# IGauge_V_2_1.net
KiCad netlist of a schematic drawn in EAGLE
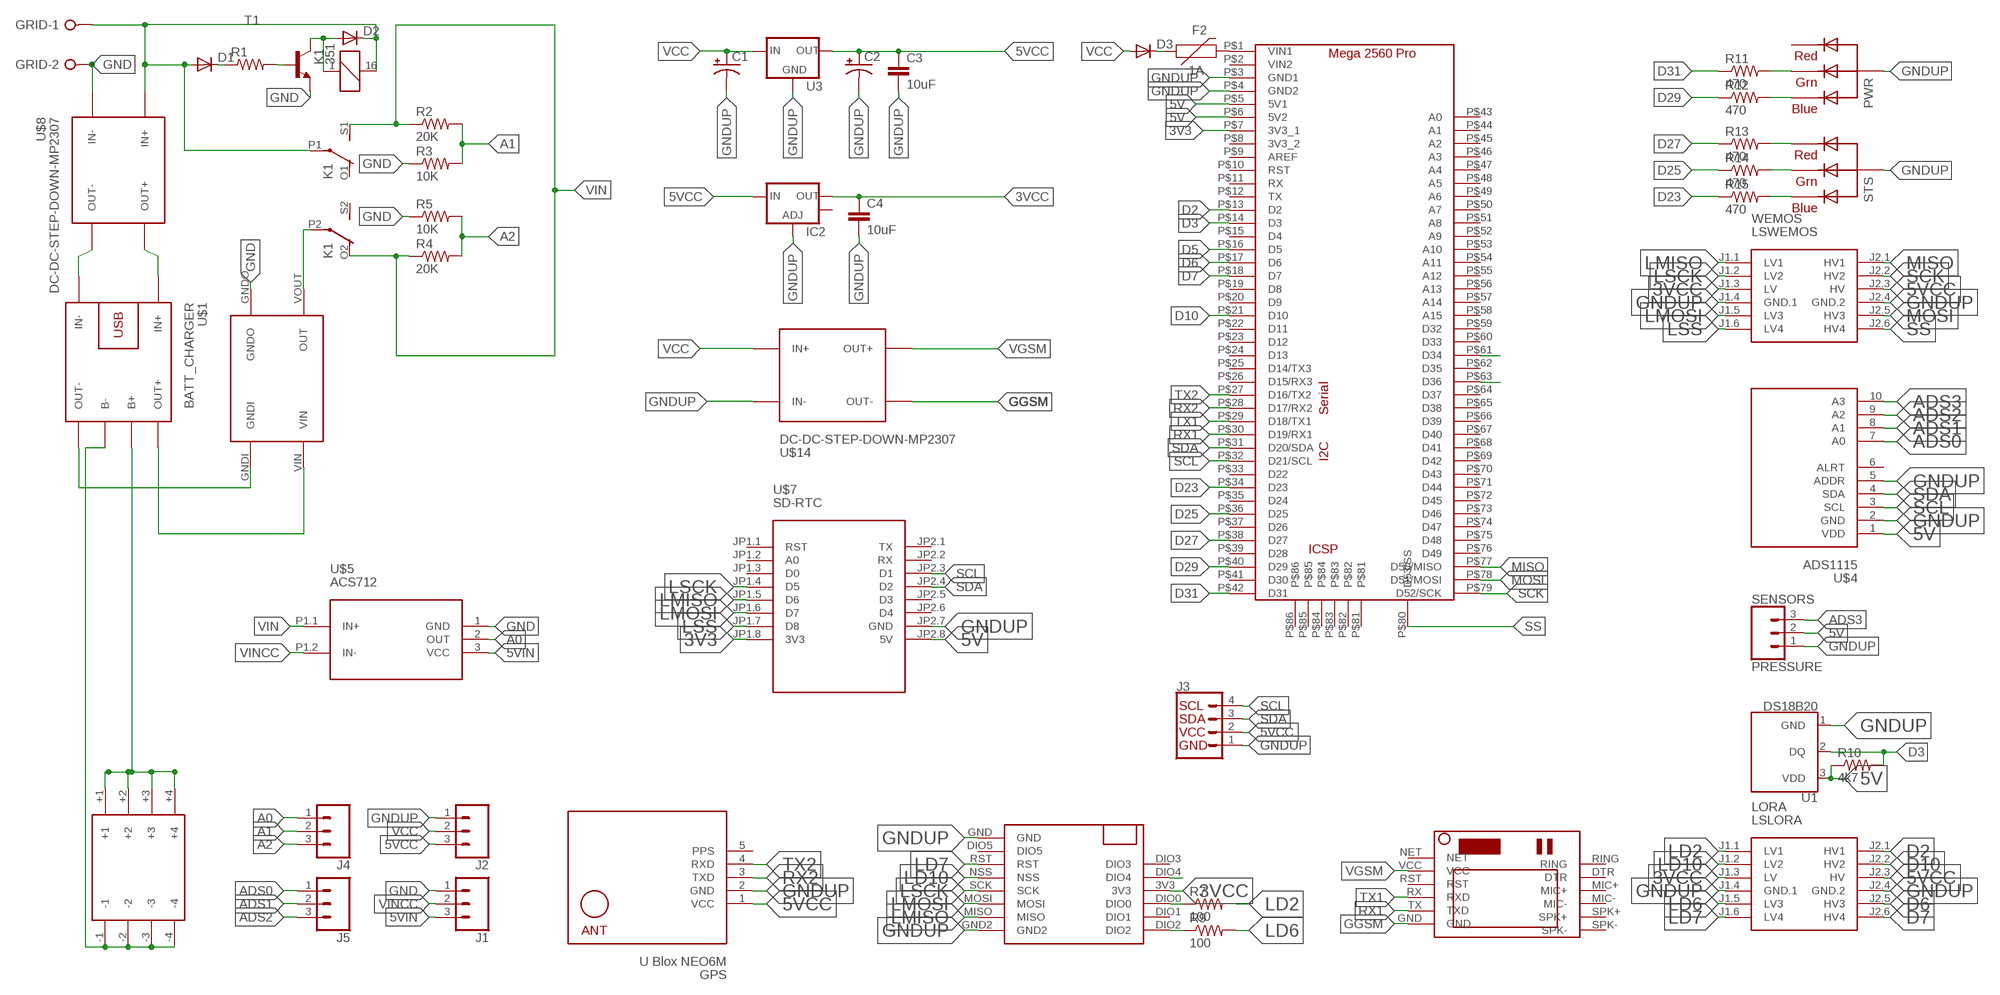
[diagram p0: schematic, sheet 1]

(export (version "E")
  (design (tool "Eeschema 10.0.6"))
  (components
    (comp (ref "C1")
      (value "CPOL-USD")
      (footprint "eagle-import:PANASONIC_D")
      (libsource (lib "eagle-import") (part "CPOL-USD"))
    )
    (comp (ref "C2")
      (value "CPOL-USD")
      (footprint "eagle-import:PANASONIC_D")
      (libsource (lib "eagle-import") (part "CPOL-USD"))
    )
    (comp (ref "C3")
      (value "10uF")
      (footprint "eagle-import:1206")
      (libsource (lib "eagle-import") (part "10UF-1206-6.3V-20%"))
    )
    (comp (ref "C4")
      (value "10uF")
      (footprint "eagle-import:1206")
      (libsource (lib "eagle-import") (part "10UF-1206-6.3V-20%"))
    )
    (comp (ref "D1")
      (value "DIODE-SOD106A-R")
      (footprint "eagle-import:SOD106A-R")
      (libsource (lib "eagle-import") (part "DIODE-SOD106A-R"))
    )
    (comp (ref "D2")
      (value "DIODE-SOD106A-R")
      (footprint "eagle-import:SOD106A-R")
      (libsource (lib "eagle-import") (part "DIODE-SOD106A-R"))
    )
    (comp (ref "D3")
      (value "DIODE-SOD106A-R")
      (footprint "eagle-import:SOD106A-R")
      (libsource (lib "eagle-import") (part "DIODE-SOD106A-R"))
    )
    (comp (ref "F2")
      (value "1A")
      (footprint "eagle-import:1206")
      (libsource (lib "eagle-import") (part "PPTC_HALF-AMP"))
    )
    (comp (ref "GPS")
      (value "U Blox NEO6M")
      (footprint "eagle-import:GPS-RECEIVER-NEO6M")
      (libsource (lib "eagle-import") (part "GPS-RECEIVER-NEO6M"))
    )
    (comp (ref "GRID")
      (value "W237-02P")
      (footprint "eagle-import:W237-132")
      (libsource (lib "eagle-import") (part "W237-02P"))
    )
    (comp (ref "IC2")
      (value "V_REG_LM1117SOT223")
      (footprint "eagle-import:SOT223")
      (libsource (lib "eagle-import") (part "V_REG_LM1117SOT223"))
    )
    (comp (ref "J1")
      (value "CONN_03")
      (footprint "eagle-import:1X03")
      (libsource (lib "eagle-import") (part "CONN_03"))
    )
    (comp (ref "J2")
      (value "CONN_03")
      (footprint "eagle-import:1X03")
      (libsource (lib "eagle-import") (part "CONN_03"))
    )
    (comp (ref "J3")
      (value "I2C_STANDARD")
      (footprint "eagle-import:1X04")
      (libsource (lib "eagle-import") (part "I2C_STANDARD"))
    )
    (comp (ref "J4")
      (value "CONN_03")
      (footprint "eagle-import:1X03")
      (libsource (lib "eagle-import") (part "CONN_03"))
    )
    (comp (ref "J5")
      (value "CONN_03")
      (footprint "eagle-import:1X03")
      (libsource (lib "eagle-import") (part "CONN_03"))
    )
    (comp (ref "K1")
      (value "351")
      (footprint "eagle-import:351")
      (libsource (lib "eagle-import") (part "351"))
    )
    (comp (ref "LORA")
      (value "LSLORA")
      (footprint "eagle-import:LEVEL-SHIFTER-4CH")
      (libsource (lib "eagle-import") (part "LEVEL-SHIFTER-4CH"))
    )
    (comp (ref "PWR")
      (value "RGBLED_CA-5MM")
      (footprint "eagle-import:LED5MMRGB")
      (libsource (lib "eagle-import") (part "RGBLED_CA-5MM"))
    )
    (comp (ref "R1")
      (value "R-US_R1206")
      (footprint "eagle-import:R1206")
      (libsource (lib "eagle-import") (part "resistor_R-US_R1206"))
    )
    (comp (ref "R2")
      (value "20K")
      (footprint "eagle-import:R1206")
      (libsource (lib "eagle-import") (part "resistor_R-US_R1206"))
    )
    (comp (ref "R3")
      (value "10K")
      (footprint "eagle-import:R1206")
      (libsource (lib "eagle-import") (part "resistor_R-US_R1206"))
    )
    (comp (ref "R4")
      (value "20K")
      (footprint "eagle-import:R1206")
      (libsource (lib "eagle-import") (part "resistor_R-US_R1206"))
    )
    (comp (ref "R5")
      (value "10K")
      (footprint "eagle-import:R1206")
      (libsource (lib "eagle-import") (part "resistor_R-US_R1206"))
    )
    (comp (ref "R7")
      (value "100")
      (footprint "eagle-import:M1406")
      (libsource (lib "eagle-import") (part "R-US_M1406"))
    )
    (comp (ref "R9")
      (value "100")
      (footprint "eagle-import:M1406")
      (libsource (lib "eagle-import") (part "R-US_M1406"))
    )
    (comp (ref "R10")
      (value "4k7")
      (footprint "eagle-import:M1406")
      (libsource (lib "eagle-import") (part "R-US_M1406"))
    )
    (comp (ref "R11")
      (value "470")
      (footprint "eagle-import:R1206")
      (libsource (lib "eagle-import") (part "resistor_R-US_R1206"))
    )
    (comp (ref "R12")
      (value "470")
      (footprint "eagle-import:R1206")
      (libsource (lib "eagle-import") (part "resistor_R-US_R1206"))
    )
    (comp (ref "R13")
      (value "470")
      (footprint "eagle-import:R1206")
      (libsource (lib "eagle-import") (part "resistor_R-US_R1206"))
    )
    (comp (ref "R14")
      (value "470")
      (footprint "eagle-import:R1206")
      (libsource (lib "eagle-import") (part "resistor_R-US_R1206"))
    )
    (comp (ref "R15")
      (value "470")
      (footprint "eagle-import:R1206")
      (libsource (lib "eagle-import") (part "resistor_R-US_R1206"))
    )
    (comp (ref "SENSORS")
      (value "PRESSURE")
      (footprint "eagle-import:MOLEX-1X3")
      (libsource (lib "eagle-import") (part "CONN_03POLAR"))
    )
    (comp (ref "STS")
      (value "RGBLED_CA-5MM")
      (footprint "eagle-import:LED5MMRGB")
      (libsource (lib "eagle-import") (part "RGBLED_CA-5MM"))
    )
    (comp (ref "T1")
      (value "-NPN-SOT23-EBC")
      (footprint "eagle-import:SOT23-EBC")
      (libsource (lib "eagle-import") (part "-NPN-SOT23-EBC"))
    )
    (comp (ref "U$1")
      (value "BATT_CHARGER")
      (footprint "eagle-import:BATTERY-CHARGER-LI-PROT")
      (libsource (lib "eagle-import") (part "BATTERY-CHARGER-LI-PROT"))
    )
    (comp (ref "U$2")
      (value "MT360_STEPUP")
      (footprint "eagle-import:MT360_STEPUP")
      (libsource (lib "eagle-import") (part "MT360_STEPUP"))
    )
    (comp (ref "U$3")
      (value "MEGAPROMINI")
      (footprint "eagle-import:MEGAPROMINI")
      (libsource (lib "eagle-import") (part "MEGAPROMINI"))
    )
    (comp (ref "U$4")
      (value "ADS1115")
      (footprint "eagle-import:ADC-4CH-ADS1115")
      (libsource (lib "eagle-import") (part "ADC-4CH-ADS1115"))
    )
    (comp (ref "U$5")
      (value "ACS712")
      (footprint "eagle-import:CURRENT-SENSOR-ACS712#IC")
      (libsource (lib "eagle-import") (part "CURRENT-SENSOR-ACS712#IC"))
    )
    (comp (ref "U$6")
      (value "LORA915MHZ")
      (footprint "eagle-import:LORA915MHZ")
      (libsource (lib "eagle-import") (part "LORA915MHZ"))
    )
    (comp (ref "U$7")
      (value "SD-RTC")
      (footprint "eagle-import:WEMOS-D1-MINI-SHIELD")
      (libsource (lib "eagle-import") (part "WEMOS-D1-MINI-SHIELD"))
    )
    (comp (ref "U$8")
      (value "DC-DC-STEP-DOWN-MP2307")
      (footprint "eagle-import:DC-DC-STEP-DOWN-MP2307")
      (libsource (lib "eagle-import") (part "DC-DC-STEP-DOWN-MP2307"))
    )
    (comp (ref "U$9")
      (value "18650_4PCS_BATTERY_HOLDER")
      (footprint "eagle-import:18650_4PCS_BATTERY_HOLDER")
      (libsource (lib "eagle-import") (part "18650_4PCS_BATTERY_HOLDER"))
    )
    (comp (ref "U$10")
      (value "SIM800LMODULE")
      (footprint "eagle-import:SIM800LMODULE")
      (libsource (lib "eagle-import") (part "SIM800LMODULE"))
    )
    (comp (ref "U$14")
      (value "DC-DC-STEP-DOWN-MP2307")
      (footprint "eagle-import:DC-DC-STEP-DOWN-MP2307")
      (libsource (lib "eagle-import") (part "DC-DC-STEP-DOWN-MP2307"))
    )
    (comp (ref "U1")
      (value "DS18B20")
      (footprint "eagle-import:TO-92-AMMO")
      (libsource (lib "eagle-import") (part "DS18B20"))
    )
    (comp (ref "U3")
      (value "V_REG_78XX-TO-220")
      (footprint "eagle-import:TO-220-ALT")
      (libsource (lib "eagle-import") (part "V_REG_78XX-TO-220"))
    )
    (comp (ref "WEMOS")
      (value "LSWEMOS")
      (footprint "eagle-import:LEVEL-SHIFTER-4CH")
      (libsource (lib "eagle-import") (part "LEVEL-SHIFTER-4CH"))
    )
  )
  (nets
    (net (code "1") (name "/PPS") (class "Default")
      (node (ref "GPS") (pin "5") (pinfunction "PPS_5") (pintype "power_in"))
    )
    (net (code "2") (name "3V3") (class "Default")
      (node (ref "U$3") (pin "P$7") (pinfunction "3V3_1_P$7") (pintype "bidirectional"))
      (node (ref "U$7") (pin "JP1.8") (pinfunction "3V3_JP1.8") (pintype "power_in"))
    )
    (net (code "3") (name "3VCC") (class "Default")
      (node (ref "C4") (pin "1") (pinfunction "1_1") (pintype "passive"))
      (node (ref "IC2") (pin "2") (pinfunction "OUT_2") (pintype "output"))
      (node (ref "LORA") (pin "J1.3") (pinfunction "LV_J1.3") (pintype "power_in"))
      (node (ref "U$6") (pin "3V3") (pinfunction "3V3_3V3") (pintype "bidirectional"))
      (node (ref "WEMOS") (pin "J1.3") (pinfunction "LV_J1.3") (pintype "power_in"))
    )
    (net (code "4") (name "5V") (class "Default")
      (node (ref "R10") (pin "1") (pinfunction "1_1") (pintype "passive"))
      (node (ref "SENSORS") (pin "2") (pinfunction "2_2") (pintype "passive"))
      (node (ref "U$3") (pin "P$5") (pinfunction "5V1_P$5") (pintype "bidirectional"))
      (node (ref "U$3") (pin "P$6") (pinfunction "5V2_P$6") (pintype "bidirectional"))
      (node (ref "U$4") (pin "1") (pinfunction "VDD_1") (pintype "power_in"))
      (node (ref "U$7") (pin "JP2.8") (pinfunction "5V_JP2.8") (pintype "power_in"))
      (node (ref "U1") (pin "3") (pinfunction "VDD_3") (pintype "power_in"))
    )
    (net (code "5") (name "5VCC") (class "Default")
      (node (ref "C2") (pin "+") (pinfunction "+_+") (pintype "passive"))
      (node (ref "C3") (pin "1") (pinfunction "1_1") (pintype "passive"))
      (node (ref "GPS") (pin "1") (pinfunction "VCC_1") (pintype "bidirectional"))
      (node (ref "IC2") (pin "3") (pinfunction "IN_3") (pintype "input"))
      (node (ref "J2") (pin "3") (pinfunction "3_3") (pintype "passive"))
      (node (ref "J3") (pin "2") (pinfunction "2_2") (pintype "power_in"))
      (node (ref "LORA") (pin "J2.3") (pinfunction "HV_J2.3") (pintype "power_in"))
      (node (ref "U3") (pin "OUT") (pinfunction "OUT_OUT") (pintype "passive"))
      (node (ref "WEMOS") (pin "J2.3") (pinfunction "HV_J2.3") (pintype "power_in"))
    )
    (net (code "6") (name "5VIN") (class "Default")
      (node (ref "J1") (pin "3") (pinfunction "3_3") (pintype "passive"))
      (node (ref "U$5") (pin "3") (pinfunction "VCC_3") (pintype "power_in"))
    )
    (net (code "7") (name "A0") (class "Default")
      (node (ref "J4") (pin "1") (pinfunction "1_1") (pintype "passive"))
      (node (ref "U$5") (pin "2") (pinfunction "OUT_2") (pintype "output"))
    )
    (net (code "8") (name "A1") (class "Default")
      (node (ref "J4") (pin "2") (pinfunction "2_2") (pintype "passive"))
      (node (ref "R2") (pin "2") (pinfunction "2_2") (pintype "passive"))
      (node (ref "R3") (pin "2") (pinfunction "2_2") (pintype "passive"))
    )
    (net (code "9") (name "A2") (class "Default")
      (node (ref "J4") (pin "3") (pinfunction "3_3") (pintype "passive"))
      (node (ref "R4") (pin "2") (pinfunction "2_2") (pintype "passive"))
      (node (ref "R5") (pin "2") (pinfunction "2_2") (pintype "passive"))
    )
    (net (code "10") (name "ADS0") (class "Default")
      (node (ref "J5") (pin "1") (pinfunction "1_1") (pintype "passive"))
      (node (ref "U$4") (pin "7") (pinfunction "A0_7") (pintype "input"))
    )
    (net (code "11") (name "ADS1") (class "Default")
      (node (ref "J5") (pin "2") (pinfunction "2_2") (pintype "passive"))
      (node (ref "U$4") (pin "8") (pinfunction "A1_8") (pintype "input"))
    )
    (net (code "12") (name "ADS2") (class "Default")
      (node (ref "J5") (pin "3") (pinfunction "3_3") (pintype "passive"))
      (node (ref "U$4") (pin "9") (pinfunction "A2_9") (pintype "input"))
    )
    (net (code "13") (name "ADS3") (class "Default")
      (node (ref "SENSORS") (pin "3") (pinfunction "3_3") (pintype "passive"))
      (node (ref "U$4") (pin "10") (pinfunction "A3_10") (pintype "input"))
    )
    (net (code "14") (name "D2") (class "Default")
      (node (ref "LORA") (pin "J2.1") (pinfunction "HV1_J2.1") (pintype "bidirectional"))
      (node (ref "U$3") (pin "P$13") (pinfunction "D2_P$13") (pintype "bidirectional"))
    )
    (net (code "15") (name "D3") (class "Default")
      (node (ref "R10") (pin "2") (pinfunction "2_2") (pintype "passive"))
      (node (ref "U$3") (pin "P$14") (pinfunction "D3_P$14") (pintype "bidirectional"))
      (node (ref "U1") (pin "2") (pinfunction "DQ_2") (pintype "bidirectional"))
    )
    (net (code "16") (name "D5") (class "Default")
      (node (ref "U$3") (pin "P$16") (pinfunction "D5_P$16") (pintype "bidirectional"))
    )
    (net (code "17") (name "D6") (class "Default")
      (node (ref "LORA") (pin "J2.5") (pinfunction "HV3_J2.5") (pintype "bidirectional"))
      (node (ref "U$3") (pin "P$17") (pinfunction "D6_P$17") (pintype "bidirectional"))
    )
    (net (code "18") (name "D7") (class "Default")
      (node (ref "LORA") (pin "J2.6") (pinfunction "HV4_J2.6") (pintype "bidirectional"))
      (node (ref "U$3") (pin "P$18") (pinfunction "D7_P$18") (pintype "bidirectional"))
    )
    (net (code "19") (name "D10") (class "Default")
      (node (ref "LORA") (pin "J2.2") (pinfunction "HV2_J2.2") (pintype "bidirectional"))
      (node (ref "U$3") (pin "P$21") (pinfunction "D10_P$21") (pintype "bidirectional"))
    )
    (net (code "20") (name "D23") (class "Default")
      (node (ref "R15") (pin "1") (pinfunction "1_1") (pintype "passive"))
      (node (ref "U$3") (pin "P$34") (pinfunction "D23_P$34") (pintype "bidirectional"))
    )
    (net (code "21") (name "D25") (class "Default")
      (node (ref "R14") (pin "1") (pinfunction "1_1") (pintype "passive"))
      (node (ref "U$3") (pin "P$36") (pinfunction "D25_P$36") (pintype "bidirectional"))
    )
    (net (code "22") (name "D27") (class "Default")
      (node (ref "R13") (pin "1") (pinfunction "1_1") (pintype "passive"))
      (node (ref "U$3") (pin "P$38") (pinfunction "D27_P$38") (pintype "bidirectional"))
    )
    (net (code "23") (name "D29") (class "Default")
      (node (ref "R12") (pin "1") (pinfunction "1_1") (pintype "passive"))
      (node (ref "U$3") (pin "P$40") (pinfunction "D29_P$40") (pintype "bidirectional"))
    )
    (net (code "24") (name "D31") (class "Default")
      (node (ref "R11") (pin "1") (pinfunction "1_1") (pintype "passive"))
      (node (ref "U$3") (pin "P$42") (pinfunction "D31_P$42") (pintype "bidirectional"))
    )
    (net (code "25") (name "GGSM") (class "Default")
      (node (ref "U$10") (pin "GND") (pinfunction "GND_GND") (pintype "bidirectional"))
      (node (ref "U$14") (pin "OUT-") (pinfunction "OUT-_OUT-") (pintype "bidirectional"))
    )
    (net (code "26") (name "GND") (class "Default")
      (node (ref "D1") (pin "A") (pinfunction "A_A") (pintype "passive"))
      (node (ref "D2") (pin "C") (pinfunction "C_C") (pintype "passive"))
      (node (ref "GRID") (pin "1") (pinfunction "KL_1") (pintype "passive"))
      (node (ref "GRID") (pin "2") (pinfunction "KL_2") (pintype "passive"))
      (node (ref "J1") (pin "1") (pinfunction "1_1") (pintype "passive"))
      (node (ref "K1") (pin "16") (pinfunction "2_16") (pintype "passive"))
      (node (ref "K1") (pin "P1") (pinfunction "P_P1") (pintype "passive"))
      (node (ref "R3") (pin "1") (pinfunction "1_1") (pintype "passive"))
      (node (ref "R5") (pin "1") (pinfunction "1_1") (pintype "passive"))
      (node (ref "T1") (pin "E") (pinfunction "E_E") (pintype "passive"))
      (node (ref "U$2") (pin "GNDO") (pinfunction "GNDO_GNDO") (pintype "bidirectional"))
      (node (ref "U$5") (pin "1") (pinfunction "GND_1") (pintype "power_in"))
      (node (ref "U$8") (pin "IN+") (pinfunction "IN+_IN+") (pintype "bidirectional"))
      (node (ref "U$8") (pin "IN-") (pinfunction "IN-_IN-") (pintype "bidirectional"))
    )
    (net (code "27") (name "GNDUP") (class "Default")
      (node (ref "C1") (pin "-") (pinfunction "-_-") (pintype "passive"))
      (node (ref "C2") (pin "-") (pinfunction "-_-") (pintype "passive"))
      (node (ref "C3") (pin "2") (pinfunction "2_2") (pintype "passive"))
      (node (ref "C4") (pin "2") (pinfunction "2_2") (pintype "passive"))
      (node (ref "GPS") (pin "2") (pinfunction "GND_2") (pintype "bidirectional"))
      (node (ref "IC2") (pin "1") (pinfunction "ADJ_1") (pintype "input"))
      (node (ref "J2") (pin "1") (pinfunction "1_1") (pintype "passive"))
      (node (ref "J3") (pin "1") (pinfunction "1_1") (pintype "power_in"))
      (node (ref "LORA") (pin "J1.4") (pinfunction "GND.1_J1.4") (pintype "power_in"))
      (node (ref "LORA") (pin "J2.4") (pinfunction "GND.2_J2.4") (pintype "power_in"))
      (node (ref "PWR") (pin "2") (pinfunction "VCC_2") (pintype "bidirectional"))
      (node (ref "SENSORS") (pin "1") (pinfunction "1_1") (pintype "passive"))
      (node (ref "STS") (pin "2") (pinfunction "VCC_2") (pintype "bidirectional"))
      (node (ref "U$1") (pin "IN-") (pinfunction "IN-_IN-") (pintype "bidirectional"))
      (node (ref "U$14") (pin "IN-") (pinfunction "IN-_IN-") (pintype "bidirectional"))
      (node (ref "U$3") (pin "P$3") (pinfunction "GND1_P$3") (pintype "bidirectional"))
      (node (ref "U$3") (pin "P$4") (pinfunction "GND2_P$4") (pintype "bidirectional"))
      (node (ref "U$4") (pin "2") (pinfunction "GND_2") (pintype "power_in"))
      (node (ref "U$4") (pin "5") (pinfunction "ADDR_5") (pintype "bidirectional"))
      (node (ref "U$6") (pin "GND") (pinfunction "GND_GND") (pintype "bidirectional"))
      (node (ref "U$6") (pin "GND2") (pinfunction "GND2_GND2") (pintype "bidirectional"))
      (node (ref "U$7") (pin "JP2.7") (pinfunction "GND_JP2.7") (pintype "power_in"))
      (node (ref "U$8") (pin "OUT-") (pinfunction "OUT-_OUT-") (pintype "bidirectional"))
      (node (ref "U1") (pin "1") (pinfunction "GND_1") (pintype "power_in"))
      (node (ref "U3") (pin "GND") (pinfunction "GND_GND") (pintype "input"))
      (node (ref "WEMOS") (pin "J1.4") (pinfunction "GND.1_J1.4") (pintype "power_in"))
      (node (ref "WEMOS") (pin "J2.4") (pinfunction "GND.2_J2.4") (pintype "power_in"))
    )
    (net (code "28") (name "LD2") (class "Default")
      (node (ref "LORA") (pin "J1.1") (pinfunction "LV1_J1.1") (pintype "bidirectional"))
      (node (ref "R7") (pin "2") (pinfunction "2_2") (pintype "passive"))
    )
    (net (code "29") (name "LD6") (class "Default")
      (node (ref "LORA") (pin "J1.5") (pinfunction "LV3_J1.5") (pintype "bidirectional"))
      (node (ref "R9") (pin "2") (pinfunction "2_2") (pintype "passive"))
    )
    (net (code "30") (name "LD7") (class "Default")
      (node (ref "LORA") (pin "J1.6") (pinfunction "LV4_J1.6") (pintype "bidirectional"))
      (node (ref "U$6") (pin "RST") (pinfunction "RST_RST") (pintype "bidirectional"))
    )
    (net (code "31") (name "LD10") (class "Default")
      (node (ref "LORA") (pin "J1.2") (pinfunction "LV2_J1.2") (pintype "bidirectional"))
      (node (ref "U$6") (pin "NSS") (pinfunction "NSS_NSS") (pintype "bidirectional"))
    )
    (net (code "32") (name "LMISO") (class "Default")
      (node (ref "U$6") (pin "MISO") (pinfunction "MISO_MISO") (pintype "bidirectional"))
      (node (ref "U$7") (pin "JP1.5") (pinfunction "D6_JP1.5") (pintype "bidirectional"))
      (node (ref "WEMOS") (pin "J1.1") (pinfunction "LV1_J1.1") (pintype "bidirectional"))
    )
    (net (code "33") (name "LMOSI") (class "Default")
      (node (ref "U$6") (pin "MOSI") (pinfunction "MOSI_MOSI") (pintype "bidirectional"))
      (node (ref "U$7") (pin "JP1.6") (pinfunction "D7_JP1.6") (pintype "bidirectional"))
      (node (ref "WEMOS") (pin "J1.5") (pinfunction "LV3_J1.5") (pintype "bidirectional"))
    )
    (net (code "34") (name "LSCK") (class "Default")
      (node (ref "U$6") (pin "SCK") (pinfunction "SCK_SCK") (pintype "bidirectional"))
      (node (ref "U$7") (pin "JP1.4") (pinfunction "D5_JP1.4") (pintype "bidirectional"))
      (node (ref "WEMOS") (pin "J1.2") (pinfunction "LV2_J1.2") (pintype "bidirectional"))
    )
    (net (code "35") (name "LSS") (class "Default")
      (node (ref "U$7") (pin "JP1.7") (pinfunction "D8_JP1.7") (pintype "bidirectional"))
      (node (ref "WEMOS") (pin "J1.6") (pinfunction "LV4_J1.6") (pintype "bidirectional"))
    )
    (net (code "36") (name "MISO") (class "Default")
      (node (ref "U$3") (pin "P$77") (pinfunction "D50/MISO_P$77") (pintype "bidirectional"))
      (node (ref "WEMOS") (pin "J2.1") (pinfunction "HV1_J2.1") (pintype "bidirectional"))
    )
    (net (code "37") (name "MOSI") (class "Default")
      (node (ref "U$3") (pin "P$78") (pinfunction "D51/MOSI_P$78") (pintype "bidirectional"))
      (node (ref "WEMOS") (pin "J2.5") (pinfunction "HV3_J2.5") (pintype "bidirectional"))
    )
    (net (code "38") (name "Net-(D1-PadC)") (class "Default")
      (node (ref "D1") (pin "C") (pinfunction "C_C") (pintype "passive"))
      (node (ref "R1") (pin "1") (pinfunction "1_1") (pintype "passive"))
    )
    (net (code "39") (name "Net-(D2-PadA)") (class "Default")
      (node (ref "D2") (pin "A") (pinfunction "A_A") (pintype "passive"))
      (node (ref "K1") (pin "1") (pinfunction "1_1") (pintype "passive"))
      (node (ref "T1") (pin "C") (pinfunction "C_C") (pintype "passive"))
    )
    (net (code "40") (name "Net-(D3-PadC)") (class "Default")
      (node (ref "D3") (pin "C") (pinfunction "C_C") (pintype "passive"))
      (node (ref "F2") (pin "1") (pinfunction "1_1") (pintype "bidirectional"))
    )
    (net (code "41") (name "Net-(K1C-P)") (class "Default")
      (node (ref "K1") (pin "P2") (pinfunction "P_P2") (pintype "passive"))
      (node (ref "U$2") (pin "VOUT") (pinfunction "OUT_VOUT") (pintype "bidirectional"))
    )
    (net (code "42") (name "Net-(PWR-BLUE)") (class "Default")
      (node (ref "PWR") (pin "4") (pinfunction "BLUE_4") (pintype "bidirectional"))
      (node (ref "R12") (pin "2") (pinfunction "2_2") (pintype "passive"))
    )
    (net (code "43") (name "Net-(PWR-GREEN)") (class "Default")
      (node (ref "PWR") (pin "3") (pinfunction "GREEN_3") (pintype "bidirectional"))
      (node (ref "R11") (pin "2") (pinfunction "2_2") (pintype "passive"))
    )
    (net (code "44") (name "Net-(R1-Pad2)") (class "Default")
      (node (ref "R1") (pin "2") (pinfunction "2_2") (pintype "passive"))
      (node (ref "T1") (pin "B") (pinfunction "B_B") (pintype "passive"))
    )
    (net (code "45") (name "Net-(R7-Pad1)") (class "Default")
      (node (ref "R7") (pin "1") (pinfunction "1_1") (pintype "passive"))
      (node (ref "U$6") (pin "DIO0") (pinfunction "DIO0_DIO0") (pintype "bidirectional"))
    )
    (net (code "46") (name "Net-(R9-Pad1)") (class "Default")
      (node (ref "R9") (pin "1") (pinfunction "1_1") (pintype "passive"))
      (node (ref "U$6") (pin "DIO2") (pinfunction "DIO2_DIO2") (pintype "bidirectional"))
    )
    (net (code "47") (name "Net-(STS-BLUE)") (class "Default")
      (node (ref "R15") (pin "2") (pinfunction "2_2") (pintype "passive"))
      (node (ref "STS") (pin "4") (pinfunction "BLUE_4") (pintype "bidirectional"))
    )
    (net (code "48") (name "Net-(STS-GREEN)") (class "Default")
      (node (ref "R14") (pin "2") (pinfunction "2_2") (pintype "passive"))
      (node (ref "STS") (pin "3") (pinfunction "GREEN_3") (pintype "bidirectional"))
    )
    (net (code "49") (name "Net-(STS-RED)") (class "Default")
      (node (ref "R13") (pin "2") (pinfunction "2_2") (pintype "passive"))
      (node (ref "STS") (pin "1") (pinfunction "RED_1") (pintype "bidirectional"))
    )
    (net (code "50") (name "Net-(U$1-PadB+)") (class "Default")
      (node (ref "U$1") (pin "B+") (pinfunction "B+_B+") (pintype "bidirectional"))
      (node (ref "U$9") (pin "+1") (pinfunction "+1_+1") (pintype "bidirectional"))
      (node (ref "U$9") (pin "+2") (pinfunction "+2_+2") (pintype "bidirectional"))
      (node (ref "U$9") (pin "+3") (pinfunction "+3_+3") (pintype "bidirectional"))
      (node (ref "U$9") (pin "+4") (pinfunction "+4_+4") (pintype "bidirectional"))
    )
    (net (code "51") (name "Net-(U$1-PadB-)") (class "Default")
      (node (ref "U$1") (pin "B-") (pinfunction "B-_B-") (pintype "bidirectional"))
      (node (ref "U$9") (pin "-1") (pinfunction "-1_-1") (pintype "bidirectional"))
      (node (ref "U$9") (pin "-2") (pinfunction "-2_-2") (pintype "bidirectional"))
      (node (ref "U$9") (pin "-3") (pinfunction "-3_-3") (pintype "bidirectional"))
      (node (ref "U$9") (pin "-4") (pinfunction "-4_-4") (pintype "bidirectional"))
    )
    (net (code "52") (name "Net-(U$1-PadIN+)") (class "Default")
      (node (ref "U$1") (pin "IN+") (pinfunction "IN+_IN+") (pintype "bidirectional"))
      (node (ref "U$8") (pin "OUT+") (pinfunction "OUT+_OUT+") (pintype "bidirectional"))
    )
    (net (code "53") (name "Net-(U$1-PadOUT+)") (class "Default")
      (node (ref "U$1") (pin "OUT+") (pinfunction "OUT+_OUT+") (pintype "bidirectional"))
      (node (ref "U$2") (pin "VIN") (pinfunction "VIN_VIN") (pintype "bidirectional"))
    )
    (net (code "54") (name "Net-(U$1-PadOUT-)") (class "Default")
      (node (ref "U$1") (pin "OUT-") (pinfunction "OUT-_OUT-") (pintype "bidirectional"))
      (node (ref "U$2") (pin "GNDI") (pinfunction "GNDI_GNDI") (pintype "bidirectional"))
    )
    (net (code "55") (name "Net-(U$3-VIN1)") (class "Default")
      (node (ref "F2") (pin "2") (pinfunction "2_2") (pintype "bidirectional"))
      (node (ref "U$3") (pin "P$1") (pinfunction "VIN1_P$1") (pintype "bidirectional"))
    )
    (net (code "56") (name "RX1") (class "Default")
      (node (ref "U$10") (pin "TX") (pinfunction "TXD_TX") (pintype "bidirectional"))
      (node (ref "U$3") (pin "P$30") (pinfunction "D19/RX1_P$30") (pintype "bidirectional"))
    )
    (net (code "57") (name "RX2") (class "Default")
      (node (ref "GPS") (pin "3") (pinfunction "TXD_3") (pintype "bidirectional"))
      (node (ref "U$3") (pin "P$28") (pinfunction "D17/RX2_P$28") (pintype "bidirectional"))
    )
    (net (code "58") (name "SCK") (class "Default")
      (node (ref "U$3") (pin "P$79") (pinfunction "D52/SCK_P$79") (pintype "bidirectional"))
      (node (ref "WEMOS") (pin "J2.2") (pinfunction "HV2_J2.2") (pintype "bidirectional"))
    )
    (net (code "59") (name "SCL") (class "Default")
      (node (ref "J3") (pin "4") (pinfunction "4_4") (pintype "passive"))
      (node (ref "U$3") (pin "P$32") (pinfunction "D21/SCL_P$32") (pintype "bidirectional"))
      (node (ref "U$4") (pin "3") (pinfunction "SCL_3") (pintype "bidirectional"))
      (node (ref "U$7") (pin "JP2.3") (pinfunction "D1_JP2.3") (pintype "bidirectional"))
    )
    (net (code "60") (name "SDA") (class "Default")
      (node (ref "J3") (pin "3") (pinfunction "3_3") (pintype "passive"))
      (node (ref "U$3") (pin "P$31") (pinfunction "D20/SDA_P$31") (pintype "bidirectional"))
      (node (ref "U$4") (pin "4") (pinfunction "SDA_4") (pintype "bidirectional"))
      (node (ref "U$7") (pin "JP2.4") (pinfunction "D2_JP2.4") (pintype "bidirectional"))
    )
    (net (code "61") (name "SS") (class "Default")
      (node (ref "U$3") (pin "P$80") (pinfunction "D53/SS_P$80") (pintype "bidirectional"))
      (node (ref "WEMOS") (pin "J2.6") (pinfunction "HV4_J2.6") (pintype "bidirectional"))
    )
    (net (code "62") (name "TX1") (class "Default")
      (node (ref "U$10") (pin "RX") (pinfunction "RXD_RX") (pintype "bidirectional"))
      (node (ref "U$3") (pin "P$29") (pinfunction "D18/TX1_P$29") (pintype "bidirectional"))
    )
    (net (code "63") (name "TX2") (class "Default")
      (node (ref "GPS") (pin "4") (pinfunction "RXD_4") (pintype "power_in"))
      (node (ref "U$3") (pin "P$27") (pinfunction "D16/TX2_P$27") (pintype "bidirectional"))
    )
    (net (code "64") (name "VCC") (class "Default")
      (node (ref "C1") (pin "+") (pinfunction "+_+") (pintype "passive"))
      (node (ref "D3") (pin "A") (pinfunction "A_A") (pintype "passive"))
      (node (ref "J2") (pin "2") (pinfunction "2_2") (pintype "passive"))
      (node (ref "U$14") (pin "IN+") (pinfunction "IN+_IN+") (pintype "bidirectional"))
      (node (ref "U3") (pin "IN") (pinfunction "IN_IN") (pintype "input"))
    )
    (net (code "65") (name "VGSM") (class "Default")
      (node (ref "U$10") (pin "VCC") (pinfunction "VCC_VCC") (pintype "bidirectional"))
      (node (ref "U$14") (pin "OUT+") (pinfunction "OUT+_OUT+") (pintype "bidirectional"))
    )
    (net (code "66") (name "VIN") (class "Default")
      (node (ref "K1") (pin "O2") (pinfunction "O_O2") (pintype "passive"))
      (node (ref "K1") (pin "S1") (pinfunction "S_S1") (pintype "passive"))
      (node (ref "R2") (pin "1") (pinfunction "1_1") (pintype "passive"))
      (node (ref "R4") (pin "1") (pinfunction "1_1") (pintype "passive"))
      (node (ref "U$5") (pin "P1.1") (pinfunction "IN+_P1.1") (pintype "bidirectional"))
    )
    (net (code "67") (name "VINCC") (class "Default")
      (node (ref "J1") (pin "2") (pinfunction "2_2") (pintype "passive"))
      (node (ref "U$5") (pin "P1.2") (pinfunction "IN-_P1.2") (pintype "bidirectional"))
    )
    (net (code "68") (name "unconnected-(IC2-OUT-Pad4)") (class "Default")
      (node (ref "IC2") (pin "4") (pinfunction "OUT_4") (pintype "output"))
    )
    (net (code "69") (name "unconnected-(K1B-O-PadO1)") (class "Default")
      (node (ref "K1") (pin "O1") (pinfunction "O_O1") (pintype "passive"))
    )
    (net (code "70") (name "unconnected-(K1C-S-PadS2)") (class "Default")
      (node (ref "K1") (pin "S2") (pinfunction "S_S2") (pintype "passive"))
    )
    (net (code "71") (name "unconnected-(PWR-RED-Pad1)") (class "Default")
      (node (ref "PWR") (pin "1") (pinfunction "RED_1") (pintype "bidirectional"))
    )
    (net (code "72") (name "unconnected-(U$3-3V3_2-PadP$8)") (class "Default")
      (node (ref "U$3") (pin "P$8") (pinfunction "3V3_2_P$8") (pintype "bidirectional"))
    )
    (net (code "73") (name "unconnected-(U$3-A0-PadP$43)") (class "Default")
      (node (ref "U$3") (pin "P$43") (pinfunction "A0_P$43") (pintype "bidirectional"))
    )
    (net (code "74") (name "unconnected-(U$3-A1-PadP$44)") (class "Default")
      (node (ref "U$3") (pin "P$44") (pinfunction "A1_P$44") (pintype "bidirectional"))
    )
    (net (code "75") (name "unconnected-(U$3-A2-PadP$45)") (class "Default")
      (node (ref "U$3") (pin "P$45") (pinfunction "A2_P$45") (pintype "bidirectional"))
    )
    (net (code "76") (name "unconnected-(U$3-A3-PadP$46)") (class "Default")
      (node (ref "U$3") (pin "P$46") (pinfunction "A3_P$46") (pintype "bidirectional"))
    )
    (net (code "77") (name "unconnected-(U$3-A4-PadP$47)") (class "Default")
      (node (ref "U$3") (pin "P$47") (pinfunction "A4_P$47") (pintype "bidirectional"))
    )
    (net (code "78") (name "unconnected-(U$3-A5-PadP$48)") (class "Default")
      (node (ref "U$3") (pin "P$48") (pinfunction "A5_P$48") (pintype "bidirectional"))
    )
    (net (code "79") (name "unconnected-(U$3-A6-PadP$49)") (class "Default")
      (node (ref "U$3") (pin "P$49") (pinfunction "A6_P$49") (pintype "bidirectional"))
    )
    (net (code "80") (name "unconnected-(U$3-A7-PadP$50)") (class "Default")
      (node (ref "U$3") (pin "P$50") (pinfunction "A7_P$50") (pintype "bidirectional"))
    )
    (net (code "81") (name "unconnected-(U$3-A8-PadP$51)") (class "Default")
      (node (ref "U$3") (pin "P$51") (pinfunction "A8_P$51") (pintype "bidirectional"))
    )
    (net (code "82") (name "unconnected-(U$3-A9-PadP$52)") (class "Default")
      (node (ref "U$3") (pin "P$52") (pinfunction "A9_P$52") (pintype "bidirectional"))
    )
    (net (code "83") (name "unconnected-(U$3-A10-PadP$53)") (class "Default")
      (node (ref "U$3") (pin "P$53") (pinfunction "A10_P$53") (pintype "bidirectional"))
    )
    (net (code "84") (name "unconnected-(U$3-A11-PadP$54)") (class "Default")
      (node (ref "U$3") (pin "P$54") (pinfunction "A11_P$54") (pintype "bidirectional"))
    )
    (net (code "85") (name "unconnected-(U$3-A12-PadP$55)") (class "Default")
      (node (ref "U$3") (pin "P$55") (pinfunction "A12_P$55") (pintype "bidirectional"))
    )
    (net (code "86") (name "unconnected-(U$3-A13-PadP$56)") (class "Default")
      (node (ref "U$3") (pin "P$56") (pinfunction "A13_P$56") (pintype "bidirectional"))
    )
    (net (code "87") (name "unconnected-(U$3-A14-PadP$57)") (class "Default")
      (node (ref "U$3") (pin "P$57") (pinfunction "A14_P$57") (pintype "bidirectional"))
    )
    (net (code "88") (name "unconnected-(U$3-A15-PadP$58)") (class "Default")
      (node (ref "U$3") (pin "P$58") (pinfunction "A15_P$58") (pintype "bidirectional"))
    )
    (net (code "89") (name "unconnected-(U$3-AREF-PadP$9)") (class "Default")
      (node (ref "U$3") (pin "P$9") (pinfunction "AREF_P$9") (pintype "bidirectional"))
    )
    (net (code "90") (name "unconnected-(U$3-D4-PadP$15)") (class "Default")
      (node (ref "U$3") (pin "P$15") (pinfunction "D4_P$15") (pintype "bidirectional"))
    )
    (net (code "91") (name "unconnected-(U$3-D8-PadP$19)") (class "Default")
      (node (ref "U$3") (pin "P$19") (pinfunction "D8_P$19") (pintype "bidirectional"))
    )
    (net (code "92") (name "unconnected-(U$3-D9-PadP$20)") (class "Default")
      (node (ref "U$3") (pin "P$20") (pinfunction "D9_P$20") (pintype "bidirectional"))
    )
    (net (code "93") (name "unconnected-(U$3-D11-PadP$22)") (class "Default")
      (node (ref "U$3") (pin "P$22") (pinfunction "D11_P$22") (pintype "bidirectional"))
    )
    (net (code "94") (name "unconnected-(U$3-D12-PadP$23)") (class "Default")
      (node (ref "U$3") (pin "P$23") (pinfunction "D12_P$23") (pintype "bidirectional"))
    )
    (net (code "95") (name "unconnected-(U$3-D13-PadP$24)") (class "Default")
      (node (ref "U$3") (pin "P$24") (pinfunction "D13_P$24") (pintype "bidirectional"))
    )
    (net (code "96") (name "unconnected-(U$3-D14{slash}TX3-PadP$25)") (class "Default")
      (node (ref "U$3") (pin "P$25") (pinfunction "D14/TX3_P$25") (pintype "bidirectional"))
    )
    (net (code "97") (name "unconnected-(U$3-D15{slash}RX3-PadP$26)") (class "Default")
      (node (ref "U$3") (pin "P$26") (pinfunction "D15/RX3_P$26") (pintype "bidirectional"))
    )
    (net (code "98") (name "unconnected-(U$3-D22-PadP$33)") (class "Default")
      (node (ref "U$3") (pin "P$33") (pinfunction "D22_P$33") (pintype "bidirectional"))
    )
    (net (code "99") (name "unconnected-(U$3-D24-PadP$35)") (class "Default")
      (node (ref "U$3") (pin "P$35") (pinfunction "D24_P$35") (pintype "bidirectional"))
    )
    (net (code "100") (name "unconnected-(U$3-D26-PadP$37)") (class "Default")
      (node (ref "U$3") (pin "P$37") (pinfunction "D26_P$37") (pintype "bidirectional"))
    )
    (net (code "101") (name "unconnected-(U$3-D28-PadP$39)") (class "Default")
      (node (ref "U$3") (pin "P$39") (pinfunction "D28_P$39") (pintype "bidirectional"))
    )
    (net (code "102") (name "unconnected-(U$3-D30-PadP$41)") (class "Default")
      (node (ref "U$3") (pin "P$41") (pinfunction "D30_P$41") (pintype "bidirectional"))
    )
    (net (code "103") (name "unconnected-(U$3-D32-PadP$59)") (class "Default")
      (node (ref "U$3") (pin "P$59") (pinfunction "D32_P$59") (pintype "bidirectional"))
    )
    (net (code "104") (name "unconnected-(U$3-D33-PadP$60)") (class "Default")
      (node (ref "U$3") (pin "P$60") (pinfunction "D33_P$60") (pintype "bidirectional"))
    )
    (net (code "105") (name "unconnected-(U$3-D34-PadP$61)") (class "Default")
      (node (ref "U$3") (pin "P$61") (pinfunction "D34_P$61") (pintype "bidirectional"))
    )
    (net (code "106") (name "unconnected-(U$3-D35-PadP$62)") (class "Default")
      (node (ref "U$3") (pin "P$62") (pinfunction "D35_P$62") (pintype "bidirectional"))
    )
    (net (code "107") (name "unconnected-(U$3-D36-PadP$63)") (class "Default")
      (node (ref "U$3") (pin "P$63") (pinfunction "D36_P$63") (pintype "bidirectional"))
    )
    (net (code "108") (name "unconnected-(U$3-D37-PadP$64)") (class "Default")
      (node (ref "U$3") (pin "P$64") (pinfunction "D37_P$64") (pintype "bidirectional"))
    )
    (net (code "109") (name "unconnected-(U$3-D38-PadP$65)") (class "Default")
      (node (ref "U$3") (pin "P$65") (pinfunction "D38_P$65") (pintype "bidirectional"))
    )
    (net (code "110") (name "unconnected-(U$3-D39-PadP$66)") (class "Default")
      (node (ref "U$3") (pin "P$66") (pinfunction "D39_P$66") (pintype "bidirectional"))
    )
    (net (code "111") (name "unconnected-(U$3-D40-PadP$67)") (class "Default")
      (node (ref "U$3") (pin "P$67") (pinfunction "D40_P$67") (pintype "bidirectional"))
    )
    (net (code "112") (name "unconnected-(U$3-D41-PadP$68)") (class "Default")
      (node (ref "U$3") (pin "P$68") (pinfunction "D41_P$68") (pintype "bidirectional"))
    )
    (net (code "113") (name "unconnected-(U$3-D42-PadP$69)") (class "Default")
      (node (ref "U$3") (pin "P$69") (pinfunction "D42_P$69") (pintype "bidirectional"))
    )
    (net (code "114") (name "unconnected-(U$3-D43-PadP$70)") (class "Default")
      (node (ref "U$3") (pin "P$70") (pinfunction "D43_P$70") (pintype "bidirectional"))
    )
    (net (code "115") (name "unconnected-(U$3-D44-PadP$71)") (class "Default")
      (node (ref "U$3") (pin "P$71") (pinfunction "D44_P$71") (pintype "bidirectional"))
    )
    (net (code "116") (name "unconnected-(U$3-D45-PadP$72)") (class "Default")
      (node (ref "U$3") (pin "P$72") (pinfunction "D45_P$72") (pintype "bidirectional"))
    )
    (net (code "117") (name "unconnected-(U$3-D46-PadP$73)") (class "Default")
      (node (ref "U$3") (pin "P$73") (pinfunction "D46_P$73") (pintype "bidirectional"))
    )
    (net (code "118") (name "unconnected-(U$3-D47-PadP$74)") (class "Default")
      (node (ref "U$3") (pin "P$74") (pinfunction "D47_P$74") (pintype "bidirectional"))
    )
    (net (code "119") (name "unconnected-(U$3-D48-PadP$75)") (class "Default")
      (node (ref "U$3") (pin "P$75") (pinfunction "D48_P$75") (pintype "bidirectional"))
    )
    (net (code "120") (name "unconnected-(U$3-D49-PadP$76)") (class "Default")
      (node (ref "U$3") (pin "P$76") (pinfunction "D49_P$76") (pintype "bidirectional"))
    )
    (net (code "121") (name "unconnected-(U$3-PadP$81)") (class "Default")
      (node (ref "U$3") (pin "P$81") (pinfunction "P$81_P$81") (pintype "bidirectional"))
    )
    (net (code "122") (name "unconnected-(U$3-PadP$82)") (class "Default")
      (node (ref "U$3") (pin "P$82") (pinfunction "P$82_P$82") (pintype "bidirectional"))
    )
    (net (code "123") (name "unconnected-(U$3-PadP$83)") (class "Default")
      (node (ref "U$3") (pin "P$83") (pinfunction "P$83_P$83") (pintype "bidirectional"))
    )
    (net (code "124") (name "unconnected-(U$3-PadP$84)") (class "Default")
      (node (ref "U$3") (pin "P$84") (pinfunction "P$84_P$84") (pintype "bidirectional"))
    )
    (net (code "125") (name "unconnected-(U$3-PadP$85)") (class "Default")
      (node (ref "U$3") (pin "P$85") (pinfunction "P$85_P$85") (pintype "bidirectional"))
    )
    (net (code "126") (name "unconnected-(U$3-PadP$86)") (class "Default")
      (node (ref "U$3") (pin "P$86") (pinfunction "P$86_P$86") (pintype "bidirectional"))
    )
    (net (code "127") (name "unconnected-(U$3-RST-PadP$10)") (class "Default")
      (node (ref "U$3") (pin "P$10") (pinfunction "RST_P$10") (pintype "bidirectional"))
    )
    (net (code "128") (name "unconnected-(U$3-RX-PadP$11)") (class "Default")
      (node (ref "U$3") (pin "P$11") (pinfunction "RX_P$11") (pintype "bidirectional"))
    )
    (net (code "129") (name "unconnected-(U$3-TX-PadP$12)") (class "Default")
      (node (ref "U$3") (pin "P$12") (pinfunction "TX_P$12") (pintype "bidirectional"))
    )
    (net (code "130") (name "unconnected-(U$3-VIN2-PadP$2)") (class "Default")
      (node (ref "U$3") (pin "P$2") (pinfunction "VIN2_P$2") (pintype "bidirectional"))
    )
    (net (code "131") (name "unconnected-(U$4-ALRT-Pad6)") (class "Default")
      (node (ref "U$4") (pin "6") (pinfunction "ALRT_6") (pintype "bidirectional"))
    )
    (net (code "132") (name "unconnected-(U$6-PadDIO1)") (class "Default")
      (node (ref "U$6") (pin "DIO1") (pinfunction "DIO1_DIO1") (pintype "bidirectional"))
    )
    (net (code "133") (name "unconnected-(U$6-PadDIO3)") (class "Default")
      (node (ref "U$6") (pin "DIO3") (pinfunction "DIO3_DIO3") (pintype "bidirectional"))
    )
    (net (code "134") (name "unconnected-(U$6-PadDIO4)") (class "Default")
      (node (ref "U$6") (pin "DIO4") (pinfunction "DIO4_DIO4") (pintype "bidirectional"))
    )
    (net (code "135") (name "unconnected-(U$6-PadDIO5)") (class "Default")
      (node (ref "U$6") (pin "DIO5") (pinfunction "DIO5_DIO5") (pintype "bidirectional"))
    )
    (net (code "136") (name "unconnected-(U$7-A0-PadJP1.2)") (class "Default")
      (node (ref "U$7") (pin "JP1.2") (pinfunction "A0_JP1.2") (pintype "bidirectional"))
    )
    (net (code "137") (name "unconnected-(U$7-D0-PadJP1.3)") (class "Default")
      (node (ref "U$7") (pin "JP1.3") (pinfunction "D0_JP1.3") (pintype "bidirectional"))
    )
    (net (code "138") (name "unconnected-(U$7-D3-PadJP2.5)") (class "Default")
      (node (ref "U$7") (pin "JP2.5") (pinfunction "D3_JP2.5") (pintype "bidirectional"))
    )
    (net (code "139") (name "unconnected-(U$7-D4-PadJP2.6)") (class "Default")
      (node (ref "U$7") (pin "JP2.6") (pinfunction "D4_JP2.6") (pintype "bidirectional"))
    )
    (net (code "140") (name "unconnected-(U$7-RST-PadJP1.1)") (class "Default")
      (node (ref "U$7") (pin "JP1.1") (pinfunction "RST_JP1.1") (pintype "bidirectional"))
    )
    (net (code "141") (name "unconnected-(U$7-RX-PadJP2.2)") (class "Default")
      (node (ref "U$7") (pin "JP2.2") (pinfunction "RX_JP2.2") (pintype "bidirectional"))
    )
    (net (code "142") (name "unconnected-(U$7-TX-PadJP2.1)") (class "Default")
      (node (ref "U$7") (pin "JP2.1") (pinfunction "TX_JP2.1") (pintype "bidirectional"))
    )
    (net (code "143") (name "unconnected-(U$10-PadDTR)") (class "Default")
      (node (ref "U$10") (pin "DTR") (pinfunction "DTR_DTR") (pintype "bidirectional"))
    )
    (net (code "144") (name "unconnected-(U$10-PadMIC+)") (class "Default")
      (node (ref "U$10") (pin "MIC+") (pinfunction "MIC+_MIC+") (pintype "bidirectional"))
    )
    (net (code "145") (name "unconnected-(U$10-PadMIC-)") (class "Default")
      (node (ref "U$10") (pin "MIC-") (pinfunction "MIC-_MIC-") (pintype "bidirectional"))
    )
    (net (code "146") (name "unconnected-(U$10-PadNET)") (class "Default")
      (node (ref "U$10") (pin "NET") (pinfunction "NET_NET") (pintype "bidirectional"))
    )
    (net (code "147") (name "unconnected-(U$10-PadRING)") (class "Default")
      (node (ref "U$10") (pin "RING") (pinfunction "RING_RING") (pintype "bidirectional"))
    )
    (net (code "148") (name "unconnected-(U$10-PadRST)") (class "Default")
      (node (ref "U$10") (pin "RST") (pinfunction "RST_RST") (pintype "bidirectional"))
    )
    (net (code "149") (name "unconnected-(U$10-PadSPK+)") (class "Default")
      (node (ref "U$10") (pin "SPK+") (pinfunction "SPK+_SPK+") (pintype "bidirectional"))
    )
    (net (code "150") (name "unconnected-(U$10-PadSPK-)") (class "Default")
      (node (ref "U$10") (pin "SPK-") (pinfunction "SPK-_SPK-") (pintype "bidirectional"))
    )
  )
)
